# pihat-v1.net
KiCad netlist of a schematic drawn in EAGLE
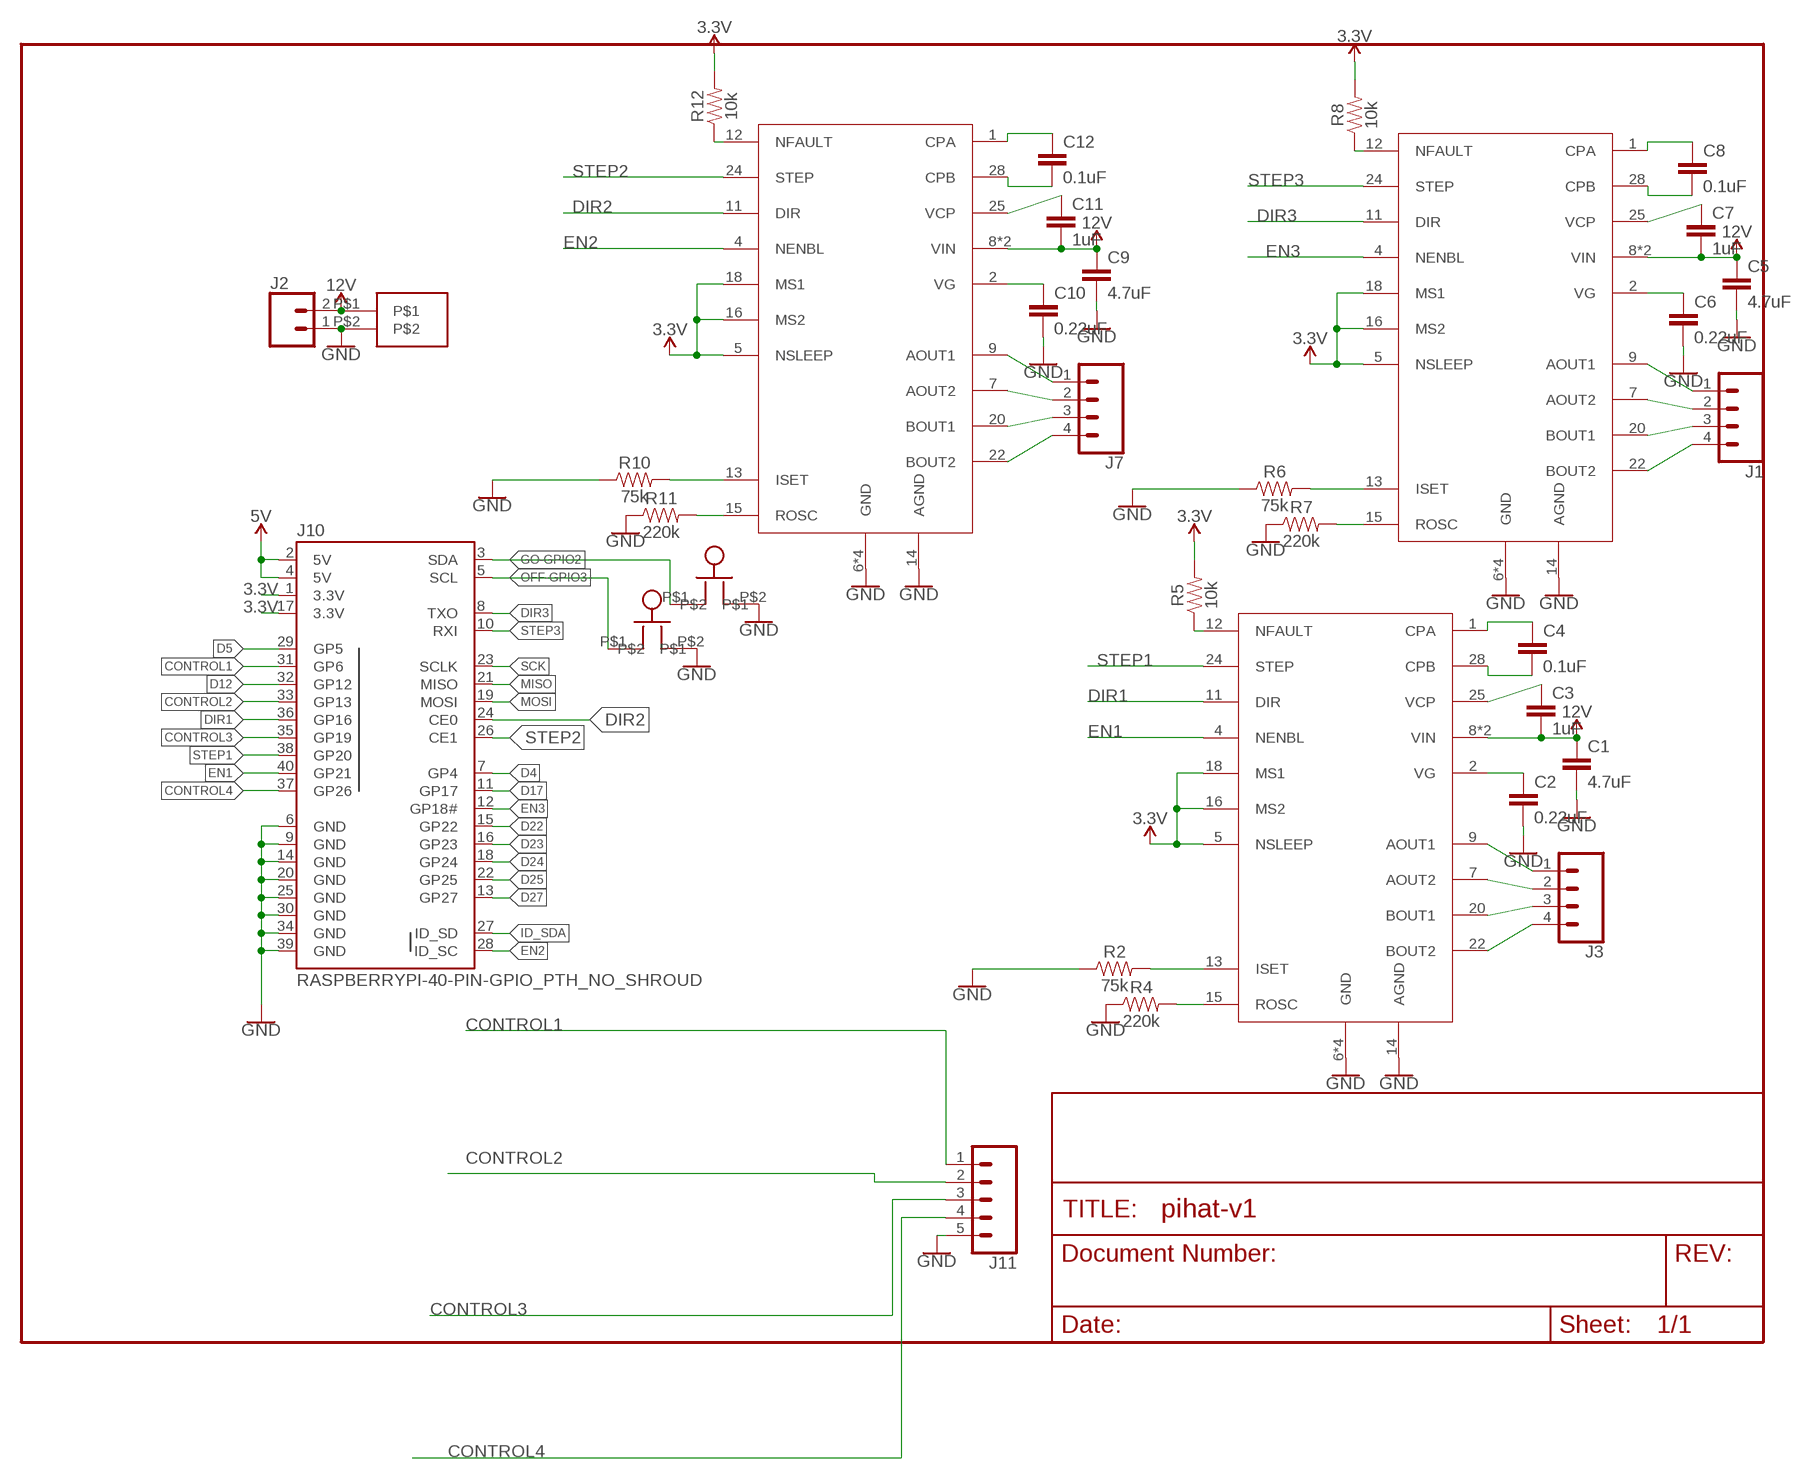
[diagram p0: schematic, sheet 1]

(export (version "E")
  (design (tool "Eeschema 10.0.6"))
  (components
    (comp (ref "C1")
      (value "4.7uF")
      (footprint "eagle-import:0603")
      (libsource (lib "eagle-import") (part "4.7UF-0603-6.3V-(10%)"))
    )
    (comp (ref "C2")
      (value "0.22uF")
      (footprint "eagle-import:0603")
      (libsource (lib "eagle-import") (part "4.7UF-0603-6.3V-(10%)"))
    )
    (comp (ref "C3")
      (value "1uF")
      (footprint "eagle-import:0603")
      (libsource (lib "eagle-import") (part "4.7UF-0603-6.3V-(10%)"))
    )
    (comp (ref "C4")
      (value "0.1uF")
      (footprint "eagle-import:0603")
      (libsource (lib "eagle-import") (part "4.7UF-0603-6.3V-(10%)"))
    )
    (comp (ref "C5")
      (value "4.7uF")
      (footprint "eagle-import:0603")
      (libsource (lib "eagle-import") (part "4.7UF-0603-6.3V-(10%)"))
    )
    (comp (ref "C6")
      (value "0.22uF")
      (footprint "eagle-import:0603")
      (libsource (lib "eagle-import") (part "4.7UF-0603-6.3V-(10%)"))
    )
    (comp (ref "C7")
      (value "1uF")
      (footprint "eagle-import:0603")
      (libsource (lib "eagle-import") (part "4.7UF-0603-6.3V-(10%)"))
    )
    (comp (ref "C8")
      (value "0.1uF")
      (footprint "eagle-import:0603")
      (libsource (lib "eagle-import") (part "4.7UF-0603-6.3V-(10%)"))
    )
    (comp (ref "C9")
      (value "4.7uF")
      (footprint "eagle-import:0603")
      (libsource (lib "eagle-import") (part "4.7UF-0603-6.3V-(10%)"))
    )
    (comp (ref "C10")
      (value "0.22uF")
      (footprint "eagle-import:0603")
      (libsource (lib "eagle-import") (part "4.7UF-0603-6.3V-(10%)"))
    )
    (comp (ref "C11")
      (value "1uF")
      (footprint "eagle-import:0603")
      (libsource (lib "eagle-import") (part "4.7UF-0603-6.3V-(10%)"))
    )
    (comp (ref "C12")
      (value "0.1uF")
      (footprint "eagle-import:0603")
      (libsource (lib "eagle-import") (part "4.7UF-0603-6.3V-(10%)"))
    )
    (comp (ref "J1")
      (value "CONN_04")
      (footprint "eagle-import:1X04")
      (libsource (lib "eagle-import") (part "CONN_04"))
    )
    (comp (ref "J2")
      (value "CONN_02")
      (footprint "eagle-import:1X02")
      (libsource (lib "eagle-import") (part "CONN_02"))
    )
    (comp (ref "J3")
      (value "CONN_04")
      (footprint "eagle-import:1X04")
      (libsource (lib "eagle-import") (part "CONN_04"))
    )
    (comp (ref "J7")
      (value "CONN_04")
      (footprint "eagle-import:1X04")
      (libsource (lib "eagle-import") (part "CONN_04"))
    )
    (comp (ref "J10")
      (value "RASPBERRYPI-40-PIN-GPIO_PTH_NO_SHROUD")
      (footprint "eagle-import:2X20")
      (libsource (lib "eagle-import") (part "RASPBERRYPI-40-PIN-GPIO_PTH_NO_SHROUD"))
    )
    (comp (ref "J11")
      (value "CONN_05")
      (footprint "eagle-import:1X05")
      (libsource (lib "eagle-import") (part "CONN_05"))
    )
    (comp (ref "R2")
      (value "75k")
      (footprint "eagle-import:0603")
      (libsource (lib "eagle-import") (part "10KOHM-0603-1/10W-1%"))
    )
    (comp (ref "R4")
      (value "220k")
      (footprint "eagle-import:0603")
      (libsource (lib "eagle-import") (part "10KOHM-0603-1/10W-1%"))
    )
    (comp (ref "R5")
      (value "10k")
      (footprint "eagle-import:0603")
      (libsource (lib "eagle-import") (part "10KOHM-0603-1/10W-1%"))
    )
    (comp (ref "R6")
      (value "75k")
      (footprint "eagle-import:0603")
      (libsource (lib "eagle-import") (part "10KOHM-0603-1/10W-1%"))
    )
    (comp (ref "R7")
      (value "220k")
      (footprint "eagle-import:0603")
      (libsource (lib "eagle-import") (part "10KOHM-0603-1/10W-1%"))
    )
    (comp (ref "R8")
      (value "10k")
      (footprint "eagle-import:0603")
      (libsource (lib "eagle-import") (part "10KOHM-0603-1/10W-1%"))
    )
    (comp (ref "R10")
      (value "75k")
      (footprint "eagle-import:0603")
      (libsource (lib "eagle-import") (part "10KOHM-0603-1/10W-1%"))
    )
    (comp (ref "R11")
      (value "220k")
      (footprint "eagle-import:0603")
      (libsource (lib "eagle-import") (part "10KOHM-0603-1/10W-1%"))
    )
    (comp (ref "R12")
      (value "10k")
      (footprint "eagle-import:0603")
      (libsource (lib "eagle-import") (part "10KOHM-0603-1/10W-1%"))
    )
    (comp (ref "U$1")
      (value "MP6500MP6500")
      (footprint "eagle-import:TSSOP28")
      (libsource (lib "eagle-import") (part "MP6500MP6500"))
    )
    (comp (ref "U$2")
      (value "MP6500MP6500")
      (footprint "eagle-import:TSSOP28")
      (libsource (lib "eagle-import") (part "MP6500MP6500"))
    )
    (comp (ref "U$3")
      (value "MP6500MP6500")
      (footprint "eagle-import:TSSOP28")
      (libsource (lib "eagle-import") (part "MP6500MP6500"))
    )
    (comp (ref "U$4")
      (value "BUTTON")
      (footprint "eagle-import:BUTTON")
      (libsource (lib "eagle-import") (part "BUTTON"))
    )
    (comp (ref "U$5")
      (value "BUTTON")
      (footprint "eagle-import:BUTTON")
      (libsource (lib "eagle-import") (part "BUTTON"))
    )
    (comp (ref "U$6")
      (value "SPRING-TERMINAL")
      (footprint "eagle-import:SPRING-TERMINAL")
      (libsource (lib "eagle-import") (part "SPRING-TERMINAL"))
    )
  )
  (nets
    (net (code "1") (name "3.3V") (class "Default")
      (node (ref "J10") (pin "1") (pinfunction "3.3V_1") (pintype "power_in"))
      (node (ref "J10") (pin "17") (pinfunction "3.3V_17") (pintype "power_in"))
      (node (ref "R12") (pin "2") (pinfunction "2_2") (pintype "passive"))
      (node (ref "R5") (pin "2") (pinfunction "2_2") (pintype "passive"))
      (node (ref "R8") (pin "2") (pinfunction "2_2") (pintype "passive"))
      (node (ref "U$1") (pin "16") (pinfunction "MS2_16") (pintype "bidirectional"))
      (node (ref "U$1") (pin "18") (pinfunction "MS1_18") (pintype "bidirectional"))
      (node (ref "U$1") (pin "5") (pinfunction "NSLEEP_5") (pintype "bidirectional"))
      (node (ref "U$2") (pin "16") (pinfunction "MS2_16") (pintype "bidirectional"))
      (node (ref "U$2") (pin "18") (pinfunction "MS1_18") (pintype "bidirectional"))
      (node (ref "U$2") (pin "5") (pinfunction "NSLEEP_5") (pintype "bidirectional"))
      (node (ref "U$3") (pin "16") (pinfunction "MS2_16") (pintype "bidirectional"))
      (node (ref "U$3") (pin "18") (pinfunction "MS1_18") (pintype "bidirectional"))
      (node (ref "U$3") (pin "5") (pinfunction "NSLEEP_5") (pintype "bidirectional"))
    )
    (net (code "2") (name "5V") (class "Default")
      (node (ref "J10") (pin "2") (pinfunction "5V_2") (pintype "power_in"))
      (node (ref "J10") (pin "4") (pinfunction "5V_4") (pintype "power_in"))
    )
    (net (code "3") (name "12V") (class "Default")
      (node (ref "C1") (pin "1") (pinfunction "1_1") (pintype "passive"))
      (node (ref "C11") (pin "2") (pinfunction "2_2") (pintype "passive"))
      (node (ref "C3") (pin "2") (pinfunction "2_2") (pintype "passive"))
      (node (ref "C5") (pin "1") (pinfunction "1_1") (pintype "passive"))
      (node (ref "C7") (pin "2") (pinfunction "2_2") (pintype "passive"))
      (node (ref "C9") (pin "1") (pinfunction "1_1") (pintype "passive"))
      (node (ref "J2") (pin "2") (pinfunction "2_2") (pintype "passive"))
      (node (ref "U$1") (pin "21") (pinfunction "VIN_21") (pintype "bidirectional"))
      (node (ref "U$1") (pin "8") (pinfunction "VIN_8") (pintype "bidirectional"))
      (node (ref "U$2") (pin "21") (pinfunction "VIN_21") (pintype "bidirectional"))
      (node (ref "U$2") (pin "8") (pinfunction "VIN_8") (pintype "bidirectional"))
      (node (ref "U$3") (pin "21") (pinfunction "VIN_21") (pintype "bidirectional"))
      (node (ref "U$3") (pin "8") (pinfunction "VIN_8") (pintype "bidirectional"))
      (node (ref "U$6") (pin "P$1") (pinfunction "P$1_P$1") (pintype "bidirectional"))
    )
    (net (code "4") (name "CONTROL1") (class "Default")
      (node (ref "J10") (pin "31") (pinfunction "GP6_31") (pintype "bidirectional"))
      (node (ref "J11") (pin "1") (pinfunction "1_1") (pintype "passive"))
    )
    (net (code "5") (name "CONTROL2") (class "Default")
      (node (ref "J10") (pin "33") (pinfunction "GP13_33") (pintype "bidirectional"))
      (node (ref "J11") (pin "2") (pinfunction "2_2") (pintype "passive"))
    )
    (net (code "6") (name "CONTROL3") (class "Default")
      (node (ref "J10") (pin "35") (pinfunction "GP19_35") (pintype "bidirectional"))
      (node (ref "J11") (pin "3") (pinfunction "3_3") (pintype "passive"))
    )
    (net (code "7") (name "CONTROL4") (class "Default")
      (node (ref "J10") (pin "37") (pinfunction "GP26_37") (pintype "bidirectional"))
      (node (ref "J11") (pin "4") (pinfunction "4_4") (pintype "passive"))
    )
    (net (code "8") (name "D4") (class "Default")
      (node (ref "J10") (pin "7") (pinfunction "GP4_7") (pintype "bidirectional"))
    )
    (net (code "9") (name "D5") (class "Default")
      (node (ref "J10") (pin "29") (pinfunction "GP5_29") (pintype "bidirectional"))
    )
    (net (code "10") (name "D12") (class "Default")
      (node (ref "J10") (pin "32") (pinfunction "GP12_32") (pintype "bidirectional"))
    )
    (net (code "11") (name "D17") (class "Default")
      (node (ref "J10") (pin "11") (pinfunction "GP17_11") (pintype "bidirectional"))
    )
    (net (code "12") (name "D22") (class "Default")
      (node (ref "J10") (pin "15") (pinfunction "GP22_15") (pintype "bidirectional"))
    )
    (net (code "13") (name "D23") (class "Default")
      (node (ref "J10") (pin "16") (pinfunction "GP23_16") (pintype "bidirectional"))
    )
    (net (code "14") (name "D24") (class "Default")
      (node (ref "J10") (pin "18") (pinfunction "GP24_18") (pintype "bidirectional"))
    )
    (net (code "15") (name "D25") (class "Default")
      (node (ref "J10") (pin "22") (pinfunction "GP25_22") (pintype "bidirectional"))
    )
    (net (code "16") (name "D27") (class "Default")
      (node (ref "J10") (pin "13") (pinfunction "GP27_13") (pintype "bidirectional"))
    )
    (net (code "17") (name "DIR1") (class "Default")
      (node (ref "J10") (pin "36") (pinfunction "GP16_36") (pintype "bidirectional"))
      (node (ref "U$3") (pin "11") (pinfunction "DIR_11") (pintype "bidirectional"))
    )
    (net (code "18") (name "DIR2") (class "Default")
      (node (ref "J10") (pin "24") (pinfunction "CE0_24") (pintype "output"))
      (node (ref "U$2") (pin "11") (pinfunction "DIR_11") (pintype "bidirectional"))
    )
    (net (code "19") (name "DIR3") (class "Default")
      (node (ref "J10") (pin "8") (pinfunction "TXO_8") (pintype "output"))
      (node (ref "U$1") (pin "11") (pinfunction "DIR_11") (pintype "bidirectional"))
    )
    (net (code "20") (name "EN1") (class "Default")
      (node (ref "J10") (pin "40") (pinfunction "GP21_40") (pintype "bidirectional"))
      (node (ref "U$3") (pin "4") (pinfunction "NENBL_4") (pintype "bidirectional"))
    )
    (net (code "21") (name "EN2") (class "Default")
      (node (ref "J10") (pin "28") (pinfunction "ID_SC_28") (pintype "bidirectional"))
      (node (ref "U$2") (pin "4") (pinfunction "NENBL_4") (pintype "bidirectional"))
    )
    (net (code "22") (name "EN3") (class "Default")
      (node (ref "J10") (pin "12") (pinfunction "GP18#_12") (pintype "bidirectional"))
      (node (ref "U$1") (pin "4") (pinfunction "NENBL_4") (pintype "bidirectional"))
    )
    (net (code "23") (name "GND") (class "Default")
      (node (ref "C1") (pin "2") (pinfunction "2_2") (pintype "passive"))
      (node (ref "C10") (pin "2") (pinfunction "2_2") (pintype "passive"))
      (node (ref "C2") (pin "2") (pinfunction "2_2") (pintype "passive"))
      (node (ref "C5") (pin "2") (pinfunction "2_2") (pintype "passive"))
      (node (ref "C6") (pin "2") (pinfunction "2_2") (pintype "passive"))
      (node (ref "C9") (pin "2") (pinfunction "2_2") (pintype "passive"))
      (node (ref "J10") (pin "14") (pinfunction "GND_14") (pintype "power_in"))
      (node (ref "J10") (pin "20") (pinfunction "GND_20") (pintype "power_in"))
      (node (ref "J10") (pin "25") (pinfunction "GND_25") (pintype "power_in"))
      (node (ref "J10") (pin "30") (pinfunction "GND_30") (pintype "power_in"))
      (node (ref "J10") (pin "34") (pinfunction "GND_34") (pintype "power_in"))
      (node (ref "J10") (pin "39") (pinfunction "GND_39") (pintype "power_in"))
      (node (ref "J10") (pin "6") (pinfunction "GND_6") (pintype "power_in"))
      (node (ref "J10") (pin "9") (pinfunction "GND_9") (pintype "power_in"))
      (node (ref "J11") (pin "5") (pinfunction "5_5") (pintype "passive"))
      (node (ref "J2") (pin "1") (pinfunction "1_1") (pintype "passive"))
      (node (ref "R10") (pin "1") (pinfunction "1_1") (pintype "passive"))
      (node (ref "R11") (pin "1") (pinfunction "1_1") (pintype "passive"))
      (node (ref "R2") (pin "1") (pinfunction "1_1") (pintype "passive"))
      (node (ref "R4") (pin "1") (pinfunction "1_1") (pintype "passive"))
      (node (ref "R6") (pin "1") (pinfunction "1_1") (pintype "passive"))
      (node (ref "R7") (pin "1") (pinfunction "1_1") (pintype "passive"))
      (node (ref "U$1") (pin "10") (pinfunction "GND_10") (pintype "bidirectional"))
      (node (ref "U$1") (pin "14") (pinfunction "AGND_14") (pintype "bidirectional"))
      (node (ref "U$1") (pin "19") (pinfunction "GND_19") (pintype "bidirectional"))
      (node (ref "U$1") (pin "23") (pinfunction "GND_23") (pintype "bidirectional"))
      (node (ref "U$1") (pin "6") (pinfunction "GND_6") (pintype "bidirectional"))
      (node (ref "U$2") (pin "10") (pinfunction "GND_10") (pintype "bidirectional"))
      (node (ref "U$2") (pin "14") (pinfunction "AGND_14") (pintype "bidirectional"))
      (node (ref "U$2") (pin "19") (pinfunction "GND_19") (pintype "bidirectional"))
      (node (ref "U$2") (pin "23") (pinfunction "GND_23") (pintype "bidirectional"))
      (node (ref "U$2") (pin "6") (pinfunction "GND_6") (pintype "bidirectional"))
      (node (ref "U$3") (pin "10") (pinfunction "GND_10") (pintype "bidirectional"))
      (node (ref "U$3") (pin "14") (pinfunction "AGND_14") (pintype "bidirectional"))
      (node (ref "U$3") (pin "19") (pinfunction "GND_19") (pintype "bidirectional"))
      (node (ref "U$3") (pin "23") (pinfunction "GND_23") (pintype "bidirectional"))
      (node (ref "U$3") (pin "6") (pinfunction "GND_6") (pintype "bidirectional"))
      (node (ref "U$4") (pin "P$2") (pinfunction "P$2_P$2") (pintype "bidirectional"))
      (node (ref "U$5") (pin "P$2") (pinfunction "P$2_P$2") (pintype "bidirectional"))
      (node (ref "U$6") (pin "P$2") (pinfunction "P$2_P$2") (pintype "bidirectional"))
    )
    (net (code "24") (name "GO-GPIO2") (class "Default")
      (node (ref "J10") (pin "3") (pinfunction "SDA_3") (pintype "bidirectional"))
      (node (ref "U$4") (pin "P$1") (pinfunction "P$1_P$1") (pintype "bidirectional"))
    )
    (net (code "25") (name "ID_SDA") (class "Default")
      (node (ref "J10") (pin "27") (pinfunction "ID_SD_27") (pintype "bidirectional"))
    )
    (net (code "26") (name "MISO") (class "Default")
      (node (ref "J10") (pin "21") (pinfunction "MISO_21") (pintype "input"))
    )
    (net (code "27") (name "MOSI") (class "Default")
      (node (ref "J10") (pin "19") (pinfunction "MOSI_19") (pintype "output"))
    )
    (net (code "28") (name "Net-(U$1-AOUT1)") (class "Default")
      (node (ref "J1") (pin "1") (pinfunction "1_1") (pintype "passive"))
      (node (ref "U$1") (pin "9") (pinfunction "AOUT1_9") (pintype "bidirectional"))
    )
    (net (code "29") (name "Net-(U$1-AOUT2)") (class "Default")
      (node (ref "J1") (pin "2") (pinfunction "2_2") (pintype "passive"))
      (node (ref "U$1") (pin "7") (pinfunction "AOUT2_7") (pintype "bidirectional"))
    )
    (net (code "30") (name "Net-(U$1-BOUT1)") (class "Default")
      (node (ref "J1") (pin "3") (pinfunction "3_3") (pintype "passive"))
      (node (ref "U$1") (pin "20") (pinfunction "BOUT1_20") (pintype "bidirectional"))
    )
    (net (code "31") (name "Net-(U$1-BOUT2)") (class "Default")
      (node (ref "J1") (pin "4") (pinfunction "4_4") (pintype "passive"))
      (node (ref "U$1") (pin "22") (pinfunction "BOUT2_22") (pintype "bidirectional"))
    )
    (net (code "32") (name "Net-(U$1-CPA)") (class "Default")
      (node (ref "C8") (pin "1") (pinfunction "1_1") (pintype "passive"))
      (node (ref "U$1") (pin "1") (pinfunction "CPA_1") (pintype "bidirectional"))
    )
    (net (code "33") (name "Net-(U$1-CPB)") (class "Default")
      (node (ref "C8") (pin "2") (pinfunction "2_2") (pintype "passive"))
      (node (ref "U$1") (pin "28") (pinfunction "CPB_28") (pintype "bidirectional"))
    )
    (net (code "34") (name "Net-(U$1-ISET)") (class "Default")
      (node (ref "R6") (pin "2") (pinfunction "2_2") (pintype "passive"))
      (node (ref "U$1") (pin "13") (pinfunction "ISET_13") (pintype "bidirectional"))
    )
    (net (code "35") (name "Net-(U$1-NFAULT)") (class "Default")
      (node (ref "R8") (pin "1") (pinfunction "1_1") (pintype "passive"))
      (node (ref "U$1") (pin "12") (pinfunction "NFAULT_12") (pintype "bidirectional"))
    )
    (net (code "36") (name "Net-(U$1-ROSC)") (class "Default")
      (node (ref "R7") (pin "2") (pinfunction "2_2") (pintype "passive"))
      (node (ref "U$1") (pin "15") (pinfunction "ROSC_15") (pintype "bidirectional"))
    )
    (net (code "37") (name "Net-(U$1-VCP)") (class "Default")
      (node (ref "C7") (pin "1") (pinfunction "1_1") (pintype "passive"))
      (node (ref "U$1") (pin "25") (pinfunction "VCP_25") (pintype "bidirectional"))
    )
    (net (code "38") (name "Net-(U$1-VG)") (class "Default")
      (node (ref "C6") (pin "1") (pinfunction "1_1") (pintype "passive"))
      (node (ref "U$1") (pin "2") (pinfunction "VG_2") (pintype "bidirectional"))
    )
    (net (code "39") (name "Net-(U$2-AOUT1)") (class "Default")
      (node (ref "J7") (pin "1") (pinfunction "1_1") (pintype "passive"))
      (node (ref "U$2") (pin "9") (pinfunction "AOUT1_9") (pintype "bidirectional"))
    )
    (net (code "40") (name "Net-(U$2-AOUT2)") (class "Default")
      (node (ref "J7") (pin "2") (pinfunction "2_2") (pintype "passive"))
      (node (ref "U$2") (pin "7") (pinfunction "AOUT2_7") (pintype "bidirectional"))
    )
    (net (code "41") (name "Net-(U$2-BOUT1)") (class "Default")
      (node (ref "J7") (pin "3") (pinfunction "3_3") (pintype "passive"))
      (node (ref "U$2") (pin "20") (pinfunction "BOUT1_20") (pintype "bidirectional"))
    )
    (net (code "42") (name "Net-(U$2-BOUT2)") (class "Default")
      (node (ref "J7") (pin "4") (pinfunction "4_4") (pintype "passive"))
      (node (ref "U$2") (pin "22") (pinfunction "BOUT2_22") (pintype "bidirectional"))
    )
    (net (code "43") (name "Net-(U$2-CPA)") (class "Default")
      (node (ref "C12") (pin "1") (pinfunction "1_1") (pintype "passive"))
      (node (ref "U$2") (pin "1") (pinfunction "CPA_1") (pintype "bidirectional"))
    )
    (net (code "44") (name "Net-(U$2-CPB)") (class "Default")
      (node (ref "C12") (pin "2") (pinfunction "2_2") (pintype "passive"))
      (node (ref "U$2") (pin "28") (pinfunction "CPB_28") (pintype "bidirectional"))
    )
    (net (code "45") (name "Net-(U$2-ISET)") (class "Default")
      (node (ref "R10") (pin "2") (pinfunction "2_2") (pintype "passive"))
      (node (ref "U$2") (pin "13") (pinfunction "ISET_13") (pintype "bidirectional"))
    )
    (net (code "46") (name "Net-(U$2-NFAULT)") (class "Default")
      (node (ref "R12") (pin "1") (pinfunction "1_1") (pintype "passive"))
      (node (ref "U$2") (pin "12") (pinfunction "NFAULT_12") (pintype "bidirectional"))
    )
    (net (code "47") (name "Net-(U$2-ROSC)") (class "Default")
      (node (ref "R11") (pin "2") (pinfunction "2_2") (pintype "passive"))
      (node (ref "U$2") (pin "15") (pinfunction "ROSC_15") (pintype "bidirectional"))
    )
    (net (code "48") (name "Net-(U$2-VCP)") (class "Default")
      (node (ref "C11") (pin "1") (pinfunction "1_1") (pintype "passive"))
      (node (ref "U$2") (pin "25") (pinfunction "VCP_25") (pintype "bidirectional"))
    )
    (net (code "49") (name "Net-(U$2-VG)") (class "Default")
      (node (ref "C10") (pin "1") (pinfunction "1_1") (pintype "passive"))
      (node (ref "U$2") (pin "2") (pinfunction "VG_2") (pintype "bidirectional"))
    )
    (net (code "50") (name "Net-(U$3-AOUT1)") (class "Default")
      (node (ref "J3") (pin "1") (pinfunction "1_1") (pintype "passive"))
      (node (ref "U$3") (pin "9") (pinfunction "AOUT1_9") (pintype "bidirectional"))
    )
    (net (code "51") (name "Net-(U$3-AOUT2)") (class "Default")
      (node (ref "J3") (pin "2") (pinfunction "2_2") (pintype "passive"))
      (node (ref "U$3") (pin "7") (pinfunction "AOUT2_7") (pintype "bidirectional"))
    )
    (net (code "52") (name "Net-(U$3-BOUT1)") (class "Default")
      (node (ref "J3") (pin "3") (pinfunction "3_3") (pintype "passive"))
      (node (ref "U$3") (pin "20") (pinfunction "BOUT1_20") (pintype "bidirectional"))
    )
    (net (code "53") (name "Net-(U$3-BOUT2)") (class "Default")
      (node (ref "J3") (pin "4") (pinfunction "4_4") (pintype "passive"))
      (node (ref "U$3") (pin "22") (pinfunction "BOUT2_22") (pintype "bidirectional"))
    )
    (net (code "54") (name "Net-(U$3-CPA)") (class "Default")
      (node (ref "C4") (pin "1") (pinfunction "1_1") (pintype "passive"))
      (node (ref "U$3") (pin "1") (pinfunction "CPA_1") (pintype "bidirectional"))
    )
    (net (code "55") (name "Net-(U$3-CPB)") (class "Default")
      (node (ref "C4") (pin "2") (pinfunction "2_2") (pintype "passive"))
      (node (ref "U$3") (pin "28") (pinfunction "CPB_28") (pintype "bidirectional"))
    )
    (net (code "56") (name "Net-(U$3-ISET)") (class "Default")
      (node (ref "R2") (pin "2") (pinfunction "2_2") (pintype "passive"))
      (node (ref "U$3") (pin "13") (pinfunction "ISET_13") (pintype "bidirectional"))
    )
    (net (code "57") (name "Net-(U$3-NFAULT)") (class "Default")
      (node (ref "R5") (pin "1") (pinfunction "1_1") (pintype "passive"))
      (node (ref "U$3") (pin "12") (pinfunction "NFAULT_12") (pintype "bidirectional"))
    )
    (net (code "58") (name "Net-(U$3-ROSC)") (class "Default")
      (node (ref "R4") (pin "2") (pinfunction "2_2") (pintype "passive"))
      (node (ref "U$3") (pin "15") (pinfunction "ROSC_15") (pintype "bidirectional"))
    )
    (net (code "59") (name "Net-(U$3-VCP)") (class "Default")
      (node (ref "C3") (pin "1") (pinfunction "1_1") (pintype "passive"))
      (node (ref "U$3") (pin "25") (pinfunction "VCP_25") (pintype "bidirectional"))
    )
    (net (code "60") (name "Net-(U$3-VG)") (class "Default")
      (node (ref "C2") (pin "1") (pinfunction "1_1") (pintype "passive"))
      (node (ref "U$3") (pin "2") (pinfunction "VG_2") (pintype "bidirectional"))
    )
    (net (code "61") (name "OFF-GPIO3") (class "Default")
      (node (ref "J10") (pin "5") (pinfunction "SCL_5") (pintype "bidirectional"))
      (node (ref "U$5") (pin "P$1") (pinfunction "P$1_P$1") (pintype "bidirectional"))
    )
    (net (code "62") (name "SCK") (class "Default")
      (node (ref "J10") (pin "23") (pinfunction "SCLK_23") (pintype "output"))
    )
    (net (code "63") (name "STEP1") (class "Default")
      (node (ref "J10") (pin "38") (pinfunction "GP20_38") (pintype "bidirectional"))
      (node (ref "U$3") (pin "24") (pinfunction "STEP_24") (pintype "bidirectional"))
    )
    (net (code "64") (name "STEP2") (class "Default")
      (node (ref "J10") (pin "26") (pinfunction "CE1_26") (pintype "output"))
      (node (ref "U$2") (pin "24") (pinfunction "STEP_24") (pintype "bidirectional"))
    )
    (net (code "65") (name "STEP3") (class "Default")
      (node (ref "J10") (pin "10") (pinfunction "RXI_10") (pintype "input"))
      (node (ref "U$1") (pin "24") (pinfunction "STEP_24") (pintype "bidirectional"))
    )
  )
)
